# schematic.net
KiCad netlist of a schematic drawn in EasyEDA
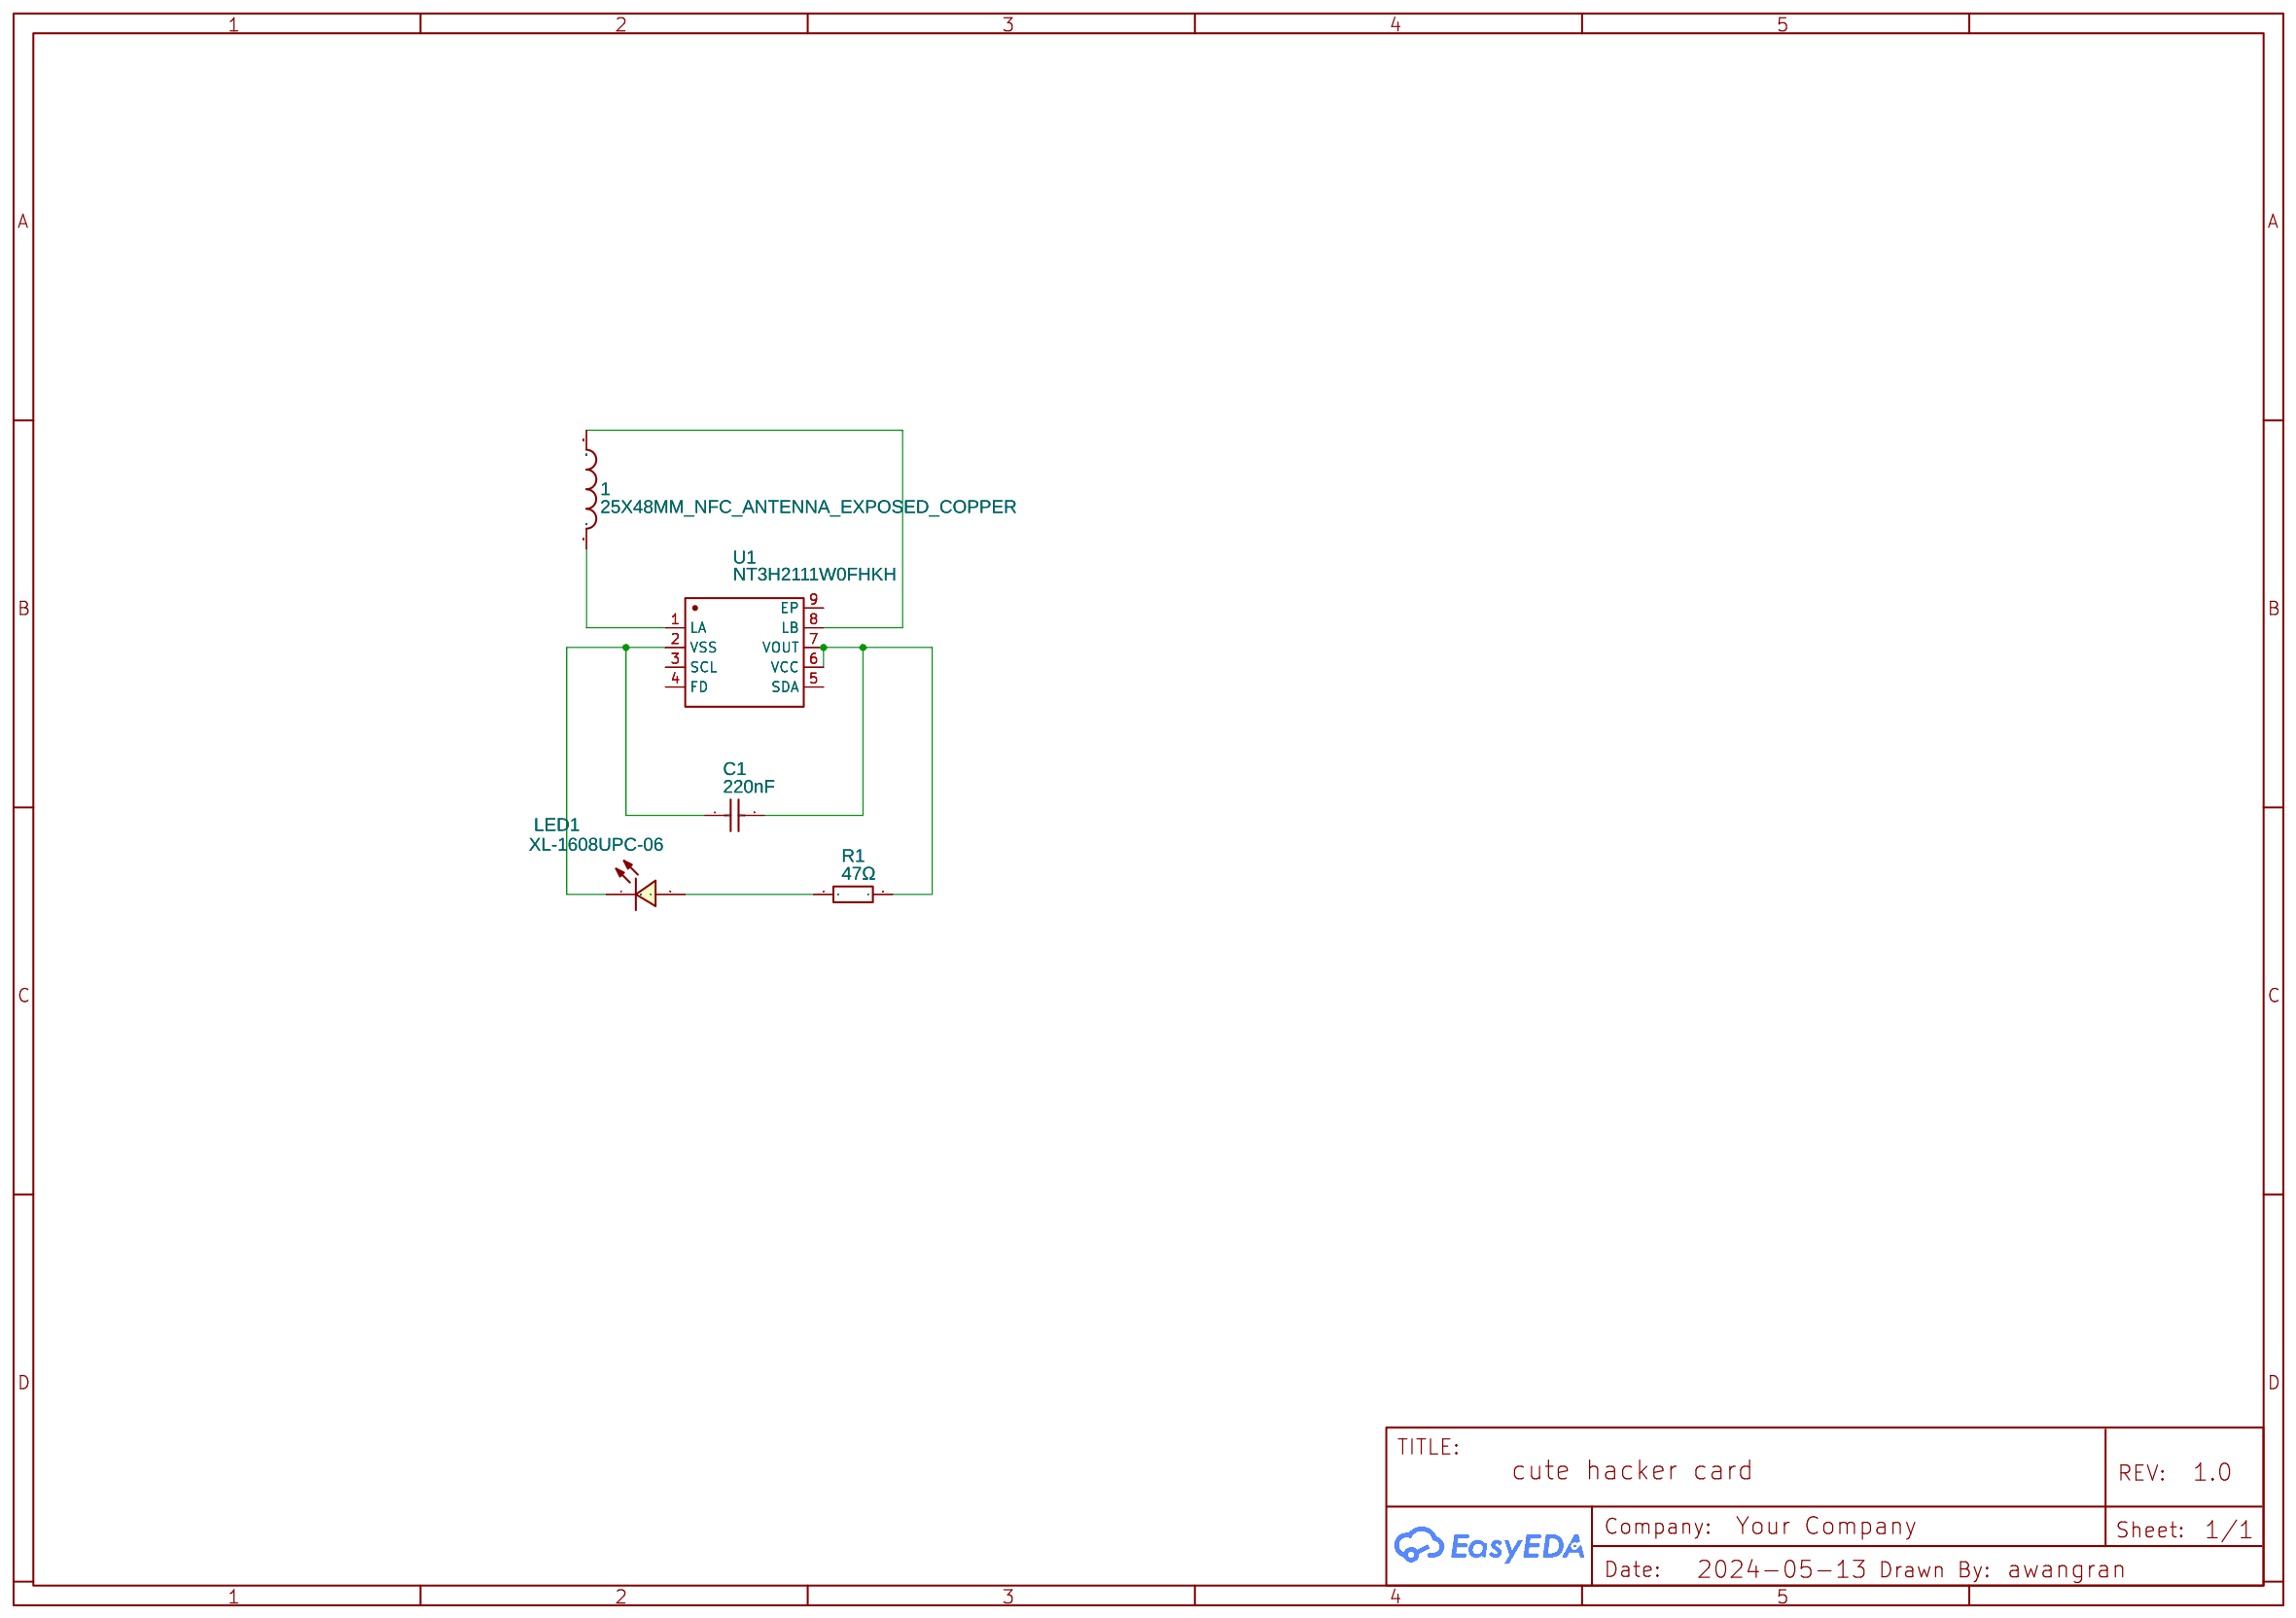
[diagram p0: schematic sheet]

(export (version "E")
  (design (tool "Eeschema 10.0.6"))
  (components
    (comp (ref "1")
      (value "25X48MM_NFC_ANTENNA_EXPOSED_COPPER")
      (libsource (lib "") (part "25X48MM_NFC_ANTENNA_EXPOSED_COPPER"))
    )
    (comp (ref "C1")
      (value "220nF")
      (fields
        (field (name "Manufacturer Part") "CL10B224KA8NNNC")
        (field (name "Manufacturer") "SAMSUNG(三星)")
      )
      (libsource (lib "") (part "CL10B224KA8NNNC"))
    )
    (comp (ref "LED1")
      (value "XL-1608UPC-06")
      (fields (field (name "Manufacturer") "XINGLIGHT(成兴光)"))
      (libsource (lib "") (part "XL-1608UPC-06"))
    )
    (comp (ref "R1")
      (value "47Ω")
      (fields
        (field (name "Manufacturer Part") "0603WAF470JT5E")
        (field (name "Manufacturer") "UNI-ROYAL(厚声)")
      )
      (libsource (lib "") (part "0603WAF470JT5E"))
    )
    (comp (ref "U1")
      (value "NT3H2111W0FHKH")
      (fields (field (name "Manufacturer") "NXP(恩智浦)"))
      (libsource (lib "") (part "NT3H2111W0FHKH"))
    )
  )
  (nets
    (net (code "1") (name "Net-(LED1-A)") (class "Default")
      (node (ref "LED1") (pin "2") (pinfunction "A_2") (pintype "unspecified"))
      (node (ref "R1") (pin "1") (pinfunction "1_1") (pintype "input"))
    )
    (net (code "2") (name "Net-(LED1-C)") (class "Default")
      (node (ref "C1") (pin "1") (pinfunction "1_1") (pintype "input"))
      (node (ref "LED1") (pin "1") (pinfunction "C_1") (pintype "unspecified"))
      (node (ref "U1") (pin "2") (pinfunction "VSS_2") (pintype "unspecified"))
    )
    (net (code "3") (name "Net-(U1-LA)") (class "Default")
      (node (ref "1") (pin "P$2") (pinfunction "P$2_P$2") (pintype "bidirectional"))
      (node (ref "U1") (pin "1") (pinfunction "LA_1") (pintype "unspecified"))
    )
    (net (code "4") (name "Net-(U1-LB)") (class "Default")
      (node (ref "1") (pin "P$1") (pinfunction "P$1_P$1") (pintype "bidirectional"))
      (node (ref "U1") (pin "8") (pinfunction "LB_8") (pintype "unspecified"))
    )
    (net (code "5") (name "Net-(U1-VCC)") (class "Default")
      (node (ref "C1") (pin "2") (pinfunction "2_2") (pintype "input"))
      (node (ref "R1") (pin "2") (pinfunction "2_2") (pintype "input"))
      (node (ref "U1") (pin "6") (pinfunction "VCC_6") (pintype "unspecified"))
      (node (ref "U1") (pin "7") (pinfunction "VOUT_7") (pintype "unspecified"))
    )
    (net (code "6") (name "unconnected-(U1-EP-Pad9)") (class "Default")
      (node (ref "U1") (pin "9") (pinfunction "EP_9") (pintype "unspecified"))
    )
    (net (code "7") (name "unconnected-(U1-FD-Pad4)") (class "Default")
      (node (ref "U1") (pin "4") (pinfunction "FD_4") (pintype "unspecified"))
    )
    (net (code "8") (name "unconnected-(U1-SCL-Pad3)") (class "Default")
      (node (ref "U1") (pin "3") (pinfunction "SCL_3") (pintype "unspecified"))
    )
    (net (code "9") (name "unconnected-(U1-SDA-Pad5)") (class "Default")
      (node (ref "U1") (pin "5") (pinfunction "SDA_5") (pintype "unspecified"))
    )
  )
)
